# DDR4.net
KiCad netlist of a schematic drawn in Altium Designer
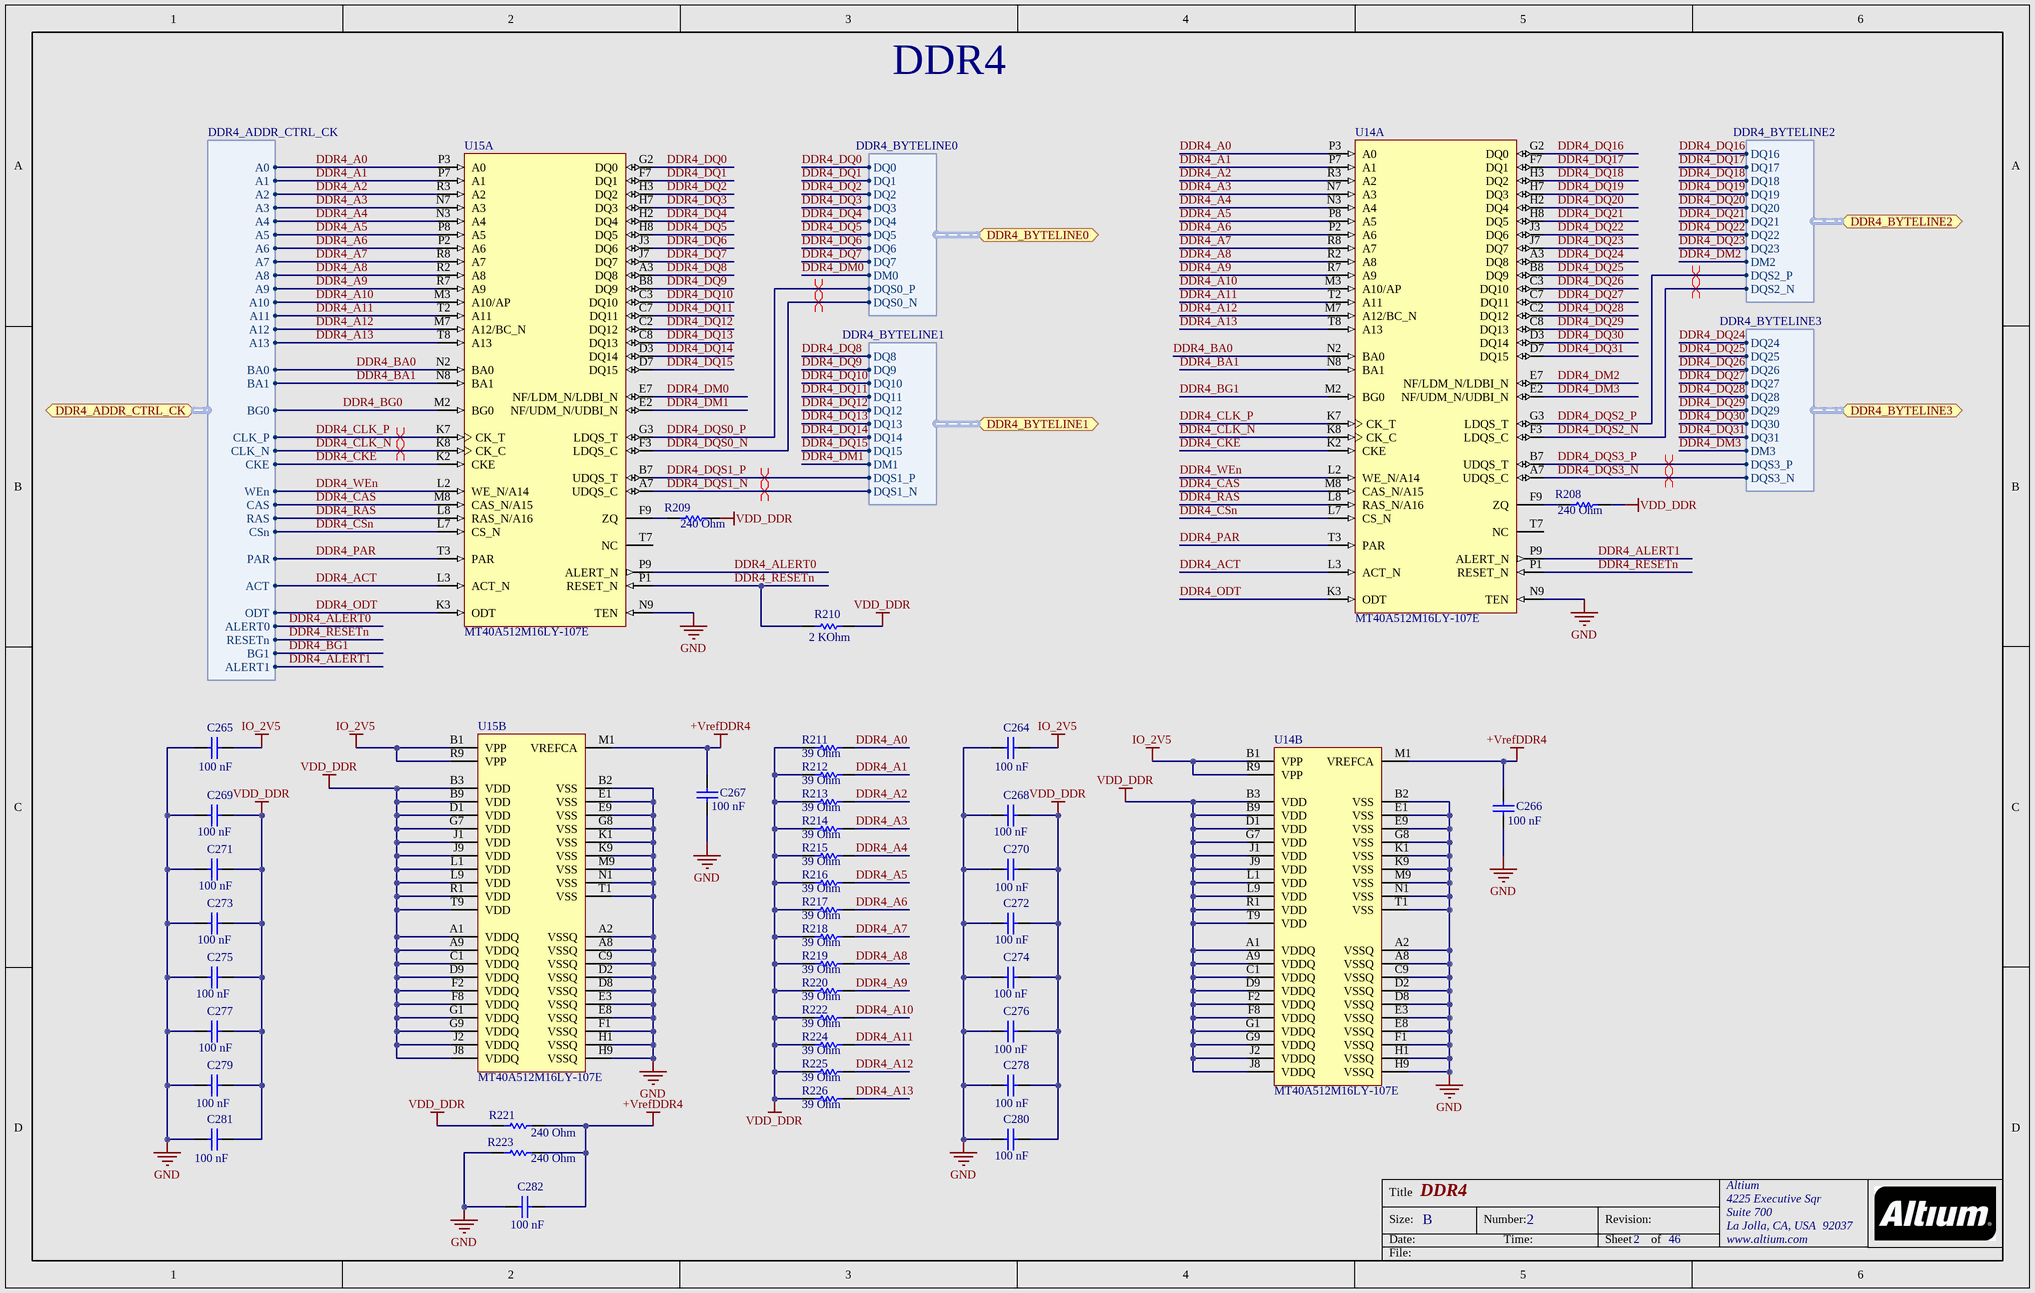
[diagram p0: DDR4.SchDoc]

(export (version "E")
  (design (tool "Eeschema 10.0.6"))
  (components
    (comp (ref "C264")
      (value "GRM033R60J104KE19D")
      (footprint "CAPC0603X33X15LL03T05")
      (description "Chip Capacitor, 100 nF, +/- 10%, 6.3 V, -55 to 85 degC, 0201 (0603 Metric), RoHS, Tape and Reel")
      (fields
        (field (name "TOLERANCE") "10%")
        (field (name "CAPACITANCE") "100 nF")
        (field (name "MANUFACTURER") "Basic Passives")
      )
      (libsource (lib "Altium Content Vault") (part "CAP-NP-2"))
    )
    (comp (ref "C265")
      (value "GRM033R60J104KE19D")
      (footprint "CAPC0603X33X15LL03T05")
      (description "Chip Capacitor, 100 nF, +/- 10%, 6.3 V, -55 to 85 degC, 0201 (0603 Metric), RoHS, Tape and Reel")
      (fields
        (field (name "TOLERANCE") "10%")
        (field (name "CAPACITANCE") "100 nF")
        (field (name "MANUFACTURER") "Basic Passives")
      )
      (libsource (lib "Altium Content Vault") (part "CAP-NP-2"))
    )
    (comp (ref "C266")
      (value "GRM033R60J104KE19D")
      (footprint "CAPC0603X33X15LL03T05")
      (description "Chip Capacitor, 100 nF, +/- 10%, 6.3 V, -55 to 85 degC, 0201 (0603 Metric), RoHS, Tape and Reel")
      (fields
        (field (name "TOLERANCE") "10%")
        (field (name "CAPACITANCE") "100 nF")
        (field (name "MANUFACTURER") "Basic Passives")
      )
      (libsource (lib "Altium Content Vault") (part "CAP-NP-2"))
    )
    (comp (ref "C267")
      (value "GRM033R60J104KE19D")
      (footprint "CAPC0603X33X15LL03T05")
      (description "Chip Capacitor, 100 nF, +/- 10%, 6.3 V, -55 to 85 degC, 0201 (0603 Metric), RoHS, Tape and Reel")
      (fields
        (field (name "TOLERANCE") "10%")
        (field (name "CAPACITANCE") "100 nF")
        (field (name "MANUFACTURER") "Basic Passives")
      )
      (libsource (lib "Altium Content Vault") (part "CAP-NP-2"))
    )
    (comp (ref "C268")
      (value "GRM033R60J104KE19D")
      (footprint "CAPC0603X33X15LL03T05")
      (description "Chip Capacitor, 100 nF, +/- 10%, 6.3 V, -55 to 85 degC, 0201 (0603 Metric), RoHS, Tape and Reel")
      (fields
        (field (name "TOLERANCE") "10%")
        (field (name "CAPACITANCE") "100 nF")
        (field (name "MANUFACTURER") "Basic Passives")
      )
      (libsource (lib "Altium Content Vault") (part "CAP-NP-2"))
    )
    (comp (ref "C269")
      (value "GRM033R60J104KE19D")
      (footprint "CAPC0603X33X15LL03T05")
      (description "Chip Capacitor, 100 nF, +/- 10%, 6.3 V, -55 to 85 degC, 0201 (0603 Metric), RoHS, Tape and Reel")
      (fields
        (field (name "TOLERANCE") "10%")
        (field (name "CAPACITANCE") "100 nF")
        (field (name "MANUFACTURER") "Basic Passives")
      )
      (libsource (lib "Altium Content Vault") (part "CAP-NP-2"))
    )
    (comp (ref "C270")
      (value "GRM033R60J104KE19D")
      (footprint "CAPC0603X33X15LL03T05")
      (description "Chip Capacitor, 100 nF, +/- 10%, 6.3 V, -55 to 85 degC, 0201 (0603 Metric), RoHS, Tape and Reel")
      (fields
        (field (name "TOLERANCE") "10%")
        (field (name "CAPACITANCE") "100 nF")
        (field (name "MANUFACTURER") "Basic Passives")
      )
      (libsource (lib "Altium Content Vault") (part "CAP-NP-2"))
    )
    (comp (ref "C271")
      (value "GRM033R60J104KE19D")
      (footprint "CAPC0603X33X15LL03T05")
      (description "Chip Capacitor, 100 nF, +/- 10%, 6.3 V, -55 to 85 degC, 0201 (0603 Metric), RoHS, Tape and Reel")
      (fields
        (field (name "TOLERANCE") "10%")
        (field (name "CAPACITANCE") "100 nF")
        (field (name "MANUFACTURER") "Basic Passives")
      )
      (libsource (lib "Altium Content Vault") (part "CAP-NP-2"))
    )
    (comp (ref "C272")
      (value "GRM033R60J104KE19D")
      (footprint "CAPC0603X33X15LL03T05")
      (description "Chip Capacitor, 100 nF, +/- 10%, 6.3 V, -55 to 85 degC, 0201 (0603 Metric), RoHS, Tape and Reel")
      (fields
        (field (name "TOLERANCE") "10%")
        (field (name "CAPACITANCE") "100 nF")
        (field (name "MANUFACTURER") "Basic Passives")
      )
      (libsource (lib "Altium Content Vault") (part "CAP-NP-2"))
    )
    (comp (ref "C273")
      (value "GRM033R60J104KE19D")
      (footprint "CAPC0603X33X15LL03T05")
      (description "Chip Capacitor, 100 nF, +/- 10%, 6.3 V, -55 to 85 degC, 0201 (0603 Metric), RoHS, Tape and Reel")
      (fields
        (field (name "TOLERANCE") "10%")
        (field (name "CAPACITANCE") "100 nF")
        (field (name "MANUFACTURER") "Basic Passives")
      )
      (libsource (lib "Altium Content Vault") (part "CAP-NP-2"))
    )
    (comp (ref "C274")
      (value "GRM033R60J104KE19D")
      (footprint "CAPC0603X33X15LL03T05")
      (description "Chip Capacitor, 100 nF, +/- 10%, 6.3 V, -55 to 85 degC, 0201 (0603 Metric), RoHS, Tape and Reel")
      (fields
        (field (name "TOLERANCE") "10%")
        (field (name "CAPACITANCE") "100 nF")
        (field (name "MANUFACTURER") "Basic Passives")
      )
      (libsource (lib "Altium Content Vault") (part "CAP-NP-2"))
    )
    (comp (ref "C275")
      (value "GRM033R60J104KE19D")
      (footprint "CAPC0603X33X15LL03T05")
      (description "Chip Capacitor, 100 nF, +/- 10%, 6.3 V, -55 to 85 degC, 0201 (0603 Metric), RoHS, Tape and Reel")
      (fields
        (field (name "TOLERANCE") "10%")
        (field (name "CAPACITANCE") "100 nF")
        (field (name "MANUFACTURER") "Basic Passives")
      )
      (libsource (lib "Altium Content Vault") (part "CAP-NP-2"))
    )
    (comp (ref "C276")
      (value "GRM033R60J104KE19D")
      (footprint "CAPC0603X33X15LL03T05")
      (description "Chip Capacitor, 100 nF, +/- 10%, 6.3 V, -55 to 85 degC, 0201 (0603 Metric), RoHS, Tape and Reel")
      (fields
        (field (name "TOLERANCE") "10%")
        (field (name "CAPACITANCE") "100 nF")
        (field (name "MANUFACTURER") "Basic Passives")
      )
      (libsource (lib "Altium Content Vault") (part "CAP-NP-2"))
    )
    (comp (ref "C277")
      (value "GRM033R60J104KE19D")
      (footprint "CAPC0603X33X15LL03T05")
      (description "Chip Capacitor, 100 nF, +/- 10%, 6.3 V, -55 to 85 degC, 0201 (0603 Metric), RoHS, Tape and Reel")
      (fields
        (field (name "TOLERANCE") "10%")
        (field (name "CAPACITANCE") "100 nF")
        (field (name "MANUFACTURER") "Basic Passives")
      )
      (libsource (lib "Altium Content Vault") (part "CAP-NP-2"))
    )
    (comp (ref "C278")
      (value "GRM033R60J104KE19D")
      (footprint "CAPC0603X33X15LL03T05")
      (description "Chip Capacitor, 100 nF, +/- 10%, 6.3 V, -55 to 85 degC, 0201 (0603 Metric), RoHS, Tape and Reel")
      (fields
        (field (name "TOLERANCE") "10%")
        (field (name "CAPACITANCE") "100 nF")
        (field (name "MANUFACTURER") "Basic Passives")
      )
      (libsource (lib "Altium Content Vault") (part "CAP-NP-2"))
    )
    (comp (ref "C279")
      (value "GRM033R60J104KE19D")
      (footprint "CAPC0603X33X15LL03T05")
      (description "Chip Capacitor, 100 nF, +/- 10%, 6.3 V, -55 to 85 degC, 0201 (0603 Metric), RoHS, Tape and Reel")
      (fields
        (field (name "TOLERANCE") "10%")
        (field (name "CAPACITANCE") "100 nF")
        (field (name "MANUFACTURER") "Basic Passives")
      )
      (libsource (lib "Altium Content Vault") (part "CAP-NP-2"))
    )
    (comp (ref "C280")
      (value "GRM033R60J104KE19D")
      (footprint "CAPC0603X33X15LL03T05")
      (description "Chip Capacitor, 100 nF, +/- 10%, 6.3 V, -55 to 85 degC, 0201 (0603 Metric), RoHS, Tape and Reel")
      (fields
        (field (name "TOLERANCE") "10%")
        (field (name "CAPACITANCE") "100 nF")
        (field (name "MANUFACTURER") "Basic Passives")
      )
      (libsource (lib "Altium Content Vault") (part "CAP-NP-2"))
    )
    (comp (ref "C281")
      (value "GRM033R60J104KE19D")
      (footprint "CAPC0603X33X15LL03T05")
      (description "Chip Capacitor, 100 nF, +/- 10%, 6.3 V, -55 to 85 degC, 0201 (0603 Metric), RoHS, Tape and Reel")
      (fields
        (field (name "TOLERANCE") "10%")
        (field (name "CAPACITANCE") "100 nF")
        (field (name "MANUFACTURER") "Basic Passives")
      )
      (libsource (lib "Altium Content Vault") (part "CAP-NP-2"))
    )
    (comp (ref "C282")
      (value "GRM033R60J104KE19D")
      (footprint "CAPC0603X33X15LL03T05")
      (description "Chip Capacitor, 100 nF, +/- 10%, 6.3 V, -55 to 85 degC, 0201 (0603 Metric), RoHS, Tape and Reel")
      (fields
        (field (name "TOLERANCE") "10%")
        (field (name "CAPACITANCE") "100 nF")
        (field (name "MANUFACTURER") "Basic Passives")
      )
      (libsource (lib "Altium Content Vault") (part "CAP-NP-2"))
    )
    (comp (ref "R208")
      (value "ERJ-2RKF2400X")
      (footprint "RESC1005X40X25NL05T05")
      (description "Chip Resistor, 240 Ohm, +/- 1%, 100 mW, -55 to 155 degC, 0402 (1005 Metric), RoHS, Tape and Reel")
      (fields (field (name "TOLERANCE") "1%") (field (name "RESISTANCE") "240 Ohm"))
      (libsource (lib "Altium Content Vault") (part "RES-2"))
    )
    (comp (ref "R209")
      (value "ERJ-2RKF2400X")
      (footprint "RESC1005X40X25NL05T05")
      (description "Chip Resistor, 240 Ohm, +/- 1%, 100 mW, -55 to 155 degC, 0402 (1005 Metric), RoHS, Tape and Reel")
      (fields (field (name "TOLERANCE") "1%") (field (name "RESISTANCE") "240 Ohm"))
      (libsource (lib "Altium Content Vault") (part "RES-2"))
    )
    (comp (ref "R210")
      (value "ERJ-2RKF2001X")
      (footprint "RESC1005X40X25NL05T05")
      (description "Chip Resistor, 2 KOhm, +/- 1%, 100 mW, -55 to 155 degC, 0402 (1005 Metric), RoHS, Tape and Reel")
      (fields
        (field (name "TOLERANCE") "1%")
        (field (name "RESISTANCE") "2 KOhm")
        (field (name "MANUFACTURER") "Basic Passives")
      )
      (libsource (lib "Altium Content Vault") (part "RES-2"))
    )
    (comp (ref "R211")
      (value "RC0402JR-0739RL")
      (footprint "RESC1005X40X25NL5T10")
      (description "Chip Resistor, 39 Ohm, +/- 5%, 0.063 W, -55 to 155 degC, 0402 (1005 Metric), RoHS, Tape and Reel")
      (fields (field (name "TOLERANCE") "5%") (field (name "RESISTANCE") "39 Ohm"))
      (libsource (lib "Altium Content Vault") (part "CMP-2002-07994-2"))
    )
    (comp (ref "R212")
      (value "RC0402JR-0739RL")
      (footprint "RESC1005X40X25NL5T10")
      (description "Chip Resistor, 39 Ohm, +/- 5%, 0.063 W, -55 to 155 degC, 0402 (1005 Metric), RoHS, Tape and Reel")
      (fields (field (name "TOLERANCE") "5%") (field (name "RESISTANCE") "39 Ohm"))
      (libsource (lib "Altium Content Vault") (part "CMP-2002-07994-2"))
    )
    (comp (ref "R213")
      (value "RC0402JR-0739RL")
      (footprint "RESC1005X40X25NL5T10")
      (description "Chip Resistor, 39 Ohm, +/- 5%, 0.063 W, -55 to 155 degC, 0402 (1005 Metric), RoHS, Tape and Reel")
      (fields (field (name "TOLERANCE") "5%") (field (name "RESISTANCE") "39 Ohm"))
      (libsource (lib "Altium Content Vault") (part "CMP-2002-07994-2"))
    )
    (comp (ref "R214")
      (value "RC0402JR-0739RL")
      (footprint "RESC1005X40X25NL5T10")
      (description "Chip Resistor, 39 Ohm, +/- 5%, 0.063 W, -55 to 155 degC, 0402 (1005 Metric), RoHS, Tape and Reel")
      (fields (field (name "TOLERANCE") "5%") (field (name "RESISTANCE") "39 Ohm"))
      (libsource (lib "Altium Content Vault") (part "CMP-2002-07994-2"))
    )
    (comp (ref "R215")
      (value "RC0402JR-0739RL")
      (footprint "RESC1005X40X25NL5T10")
      (description "Chip Resistor, 39 Ohm, +/- 5%, 0.063 W, -55 to 155 degC, 0402 (1005 Metric), RoHS, Tape and Reel")
      (fields (field (name "TOLERANCE") "5%") (field (name "RESISTANCE") "39 Ohm"))
      (libsource (lib "Altium Content Vault") (part "CMP-2002-07994-2"))
    )
    (comp (ref "R216")
      (value "RC0402JR-0739RL")
      (footprint "RESC1005X40X25NL5T10")
      (description "Chip Resistor, 39 Ohm, +/- 5%, 0.063 W, -55 to 155 degC, 0402 (1005 Metric), RoHS, Tape and Reel")
      (fields (field (name "TOLERANCE") "5%") (field (name "RESISTANCE") "39 Ohm"))
      (libsource (lib "Altium Content Vault") (part "CMP-2002-07994-2"))
    )
    (comp (ref "R217")
      (value "RC0402JR-0739RL")
      (footprint "RESC1005X40X25NL5T10")
      (description "Chip Resistor, 39 Ohm, +/- 5%, 0.063 W, -55 to 155 degC, 0402 (1005 Metric), RoHS, Tape and Reel")
      (fields (field (name "TOLERANCE") "5%") (field (name "RESISTANCE") "39 Ohm"))
      (libsource (lib "Altium Content Vault") (part "CMP-2002-07994-2"))
    )
    (comp (ref "R218")
      (value "RC0402JR-0739RL")
      (footprint "RESC1005X40X25NL5T10")
      (description "Chip Resistor, 39 Ohm, +/- 5%, 0.063 W, -55 to 155 degC, 0402 (1005 Metric), RoHS, Tape and Reel")
      (fields (field (name "TOLERANCE") "5%") (field (name "RESISTANCE") "39 Ohm"))
      (libsource (lib "Altium Content Vault") (part "CMP-2002-07994-2"))
    )
    (comp (ref "R219")
      (value "RC0402JR-0739RL")
      (footprint "RESC1005X40X25NL5T10")
      (description "Chip Resistor, 39 Ohm, +/- 5%, 0.063 W, -55 to 155 degC, 0402 (1005 Metric), RoHS, Tape and Reel")
      (fields (field (name "TOLERANCE") "5%") (field (name "RESISTANCE") "39 Ohm"))
      (libsource (lib "Altium Content Vault") (part "CMP-2002-07994-2"))
    )
    (comp (ref "R220")
      (value "RC0402JR-0739RL")
      (footprint "RESC1005X40X25NL5T10")
      (description "Chip Resistor, 39 Ohm, +/- 5%, 0.063 W, -55 to 155 degC, 0402 (1005 Metric), RoHS, Tape and Reel")
      (fields (field (name "TOLERANCE") "5%") (field (name "RESISTANCE") "39 Ohm"))
      (libsource (lib "Altium Content Vault") (part "CMP-2002-07994-2"))
    )
    (comp (ref "R221")
      (value "ERJ-2RKF2400X")
      (footprint "RESC1005X40X25NL05T05")
      (description "Chip Resistor, 240 Ohm, +/- 1%, 100 mW, -55 to 155 degC, 0402 (1005 Metric), RoHS, Tape and Reel")
      (fields (field (name "TOLERANCE") "1%") (field (name "RESISTANCE") "240 Ohm"))
      (libsource (lib "Altium Content Vault") (part "RES-2"))
    )
    (comp (ref "R222")
      (value "RC0402JR-0739RL")
      (footprint "RESC1005X40X25NL5T10")
      (description "Chip Resistor, 39 Ohm, +/- 5%, 0.063 W, -55 to 155 degC, 0402 (1005 Metric), RoHS, Tape and Reel")
      (fields (field (name "TOLERANCE") "5%") (field (name "RESISTANCE") "39 Ohm"))
      (libsource (lib "Altium Content Vault") (part "CMP-2002-07994-2"))
    )
    (comp (ref "R223")
      (value "ERJ-2RKF2400X")
      (footprint "RESC1005X40X25NL05T05")
      (description "Chip Resistor, 240 Ohm, +/- 1%, 100 mW, -55 to 155 degC, 0402 (1005 Metric), RoHS, Tape and Reel")
      (fields (field (name "TOLERANCE") "1%") (field (name "RESISTANCE") "240 Ohm"))
      (libsource (lib "Altium Content Vault") (part "RES-2"))
    )
    (comp (ref "R224")
      (value "RC0402JR-0739RL")
      (footprint "RESC1005X40X25NL5T10")
      (description "Chip Resistor, 39 Ohm, +/- 5%, 0.063 W, -55 to 155 degC, 0402 (1005 Metric), RoHS, Tape and Reel")
      (fields (field (name "TOLERANCE") "5%") (field (name "RESISTANCE") "39 Ohm"))
      (libsource (lib "Altium Content Vault") (part "CMP-2002-07994-2"))
    )
    (comp (ref "R225")
      (value "RC0402JR-0739RL")
      (footprint "RESC1005X40X25NL5T10")
      (description "Chip Resistor, 39 Ohm, +/- 5%, 0.063 W, -55 to 155 degC, 0402 (1005 Metric), RoHS, Tape and Reel")
      (fields (field (name "TOLERANCE") "5%") (field (name "RESISTANCE") "39 Ohm"))
      (libsource (lib "Altium Content Vault") (part "CMP-2002-07994-2"))
    )
    (comp (ref "R226")
      (value "RC0402JR-0739RL")
      (footprint "RESC1005X40X25NL5T10")
      (description "Chip Resistor, 39 Ohm, +/- 5%, 0.063 W, -55 to 155 degC, 0402 (1005 Metric), RoHS, Tape and Reel")
      (fields (field (name "TOLERANCE") "5%") (field (name "RESISTANCE") "39 Ohm"))
      (libsource (lib "Altium Content Vault") (part "CMP-2002-07994-2"))
    )
    (comp (ref "U14")
      (value "MT40A512M16LY-107E")
      (footprint "MICT-LY-96_A")
      (description "8 Gb DDR4 SDRAM, 512 Meg x 16, 1.2 V, 0 to 95 degC, 96-Ball FBGA (LY), RoHS")
      (libsource (lib "Altium Content Vault") (part "CMP-1718-00002-1"))
    )
    (comp (ref "U15")
      (value "MT40A512M16LY-107E")
      (footprint "MICT-LY-96_A")
      (description "8 Gb DDR4 SDRAM, 512 Meg x 16, 1.2 V, 0 to 95 degC, 96-Ball FBGA (LY), RoHS")
      (libsource (lib "Altium Content Vault") (part "CMP-1718-00002-1"))
    )
  )
  (nets
    (net (code "6") (name "+VrefDDR4") (class "Default")
      (node (ref "C266") (pin "2") (pinfunction "2_2") (pintype "passive"))
      (node (ref "C267") (pin "2") (pinfunction "2_2") (pintype "passive"))
      (node (ref "C282") (pin "2") (pinfunction "2_2") (pintype "passive"))
      (node (ref "R221") (pin "2") (pinfunction "2_2") (pintype "passive"))
      (node (ref "R223") (pin "2") (pinfunction "2_2") (pintype "passive"))
      (node (ref "U14") (pin "M1") (pinfunction "VREFCA_M1") (pintype "passive"))
      (node (ref "U15") (pin "M1") (pinfunction "VREFCA_M1") (pintype "passive"))
    )
    (net (code "7") (name "/DDR4_A0") (class "Default")
      (node (ref "R211") (pin "2") (pinfunction "2_2") (pintype "passive"))
      (node (ref "U14") (pin "P3") (pinfunction "A0_P3") (pintype "input"))
      (node (ref "U15") (pin "P3") (pinfunction "A0_P3") (pintype "input"))
    )
    (net (code "8") (name "/DDR4_A1") (class "Default")
      (node (ref "R212") (pin "2") (pinfunction "2_2") (pintype "passive"))
      (node (ref "U14") (pin "P7") (pinfunction "A1_P7") (pintype "input"))
      (node (ref "U15") (pin "P7") (pinfunction "A1_P7") (pintype "input"))
    )
    (net (code "9") (name "/DDR4_A2") (class "Default")
      (node (ref "R213") (pin "2") (pinfunction "2_2") (pintype "passive"))
      (node (ref "U14") (pin "R3") (pinfunction "A2_R3") (pintype "input"))
      (node (ref "U15") (pin "R3") (pinfunction "A2_R3") (pintype "input"))
    )
    (net (code "10") (name "/DDR4_A3") (class "Default")
      (node (ref "R214") (pin "2") (pinfunction "2_2") (pintype "passive"))
      (node (ref "U14") (pin "N7") (pinfunction "A3_N7") (pintype "input"))
      (node (ref "U15") (pin "N7") (pinfunction "A3_N7") (pintype "input"))
    )
    (net (code "11") (name "/DDR4_A4") (class "Default")
      (node (ref "R215") (pin "2") (pinfunction "2_2") (pintype "passive"))
      (node (ref "U14") (pin "N3") (pinfunction "A4_N3") (pintype "input"))
      (node (ref "U15") (pin "N3") (pinfunction "A4_N3") (pintype "input"))
    )
    (net (code "12") (name "/DDR4_A5") (class "Default")
      (node (ref "R216") (pin "2") (pinfunction "2_2") (pintype "passive"))
      (node (ref "U14") (pin "P8") (pinfunction "A5_P8") (pintype "input"))
      (node (ref "U15") (pin "P8") (pinfunction "A5_P8") (pintype "input"))
    )
    (net (code "13") (name "/DDR4_A6") (class "Default")
      (node (ref "R217") (pin "2") (pinfunction "2_2") (pintype "passive"))
      (node (ref "U14") (pin "P2") (pinfunction "A6_P2") (pintype "input"))
      (node (ref "U15") (pin "P2") (pinfunction "A6_P2") (pintype "input"))
    )
    (net (code "14") (name "/DDR4_A7") (class "Default")
      (node (ref "R218") (pin "2") (pinfunction "2_2") (pintype "passive"))
      (node (ref "U14") (pin "R8") (pinfunction "A7_R8") (pintype "input"))
      (node (ref "U15") (pin "R8") (pinfunction "A7_R8") (pintype "input"))
    )
    (net (code "15") (name "/DDR4_A8") (class "Default")
      (node (ref "R219") (pin "2") (pinfunction "2_2") (pintype "passive"))
      (node (ref "U14") (pin "R2") (pinfunction "A8_R2") (pintype "input"))
      (node (ref "U15") (pin "R2") (pinfunction "A8_R2") (pintype "input"))
    )
    (net (code "16") (name "/DDR4_A9") (class "Default")
      (node (ref "R220") (pin "2") (pinfunction "2_2") (pintype "passive"))
      (node (ref "U14") (pin "R7") (pinfunction "A9_R7") (pintype "input"))
      (node (ref "U15") (pin "R7") (pinfunction "A9_R7") (pintype "input"))
    )
    (net (code "17") (name "/DDR4_A10") (class "Default")
      (node (ref "R222") (pin "2") (pinfunction "2_2") (pintype "passive"))
      (node (ref "U14") (pin "M3") (pinfunction "A10/AP_M3") (pintype "input"))
      (node (ref "U15") (pin "M3") (pinfunction "A10/AP_M3") (pintype "input"))
    )
    (net (code "18") (name "/DDR4_A11") (class "Default")
      (node (ref "R224") (pin "2") (pinfunction "2_2") (pintype "passive"))
      (node (ref "U14") (pin "T2") (pinfunction "A11_T2") (pintype "input"))
      (node (ref "U15") (pin "T2") (pinfunction "A11_T2") (pintype "input"))
    )
    (net (code "19") (name "/DDR4_A12") (class "Default")
      (node (ref "R225") (pin "2") (pinfunction "2_2") (pintype "passive"))
      (node (ref "U14") (pin "M7") (pinfunction "A12/BC_N_M7") (pintype "input"))
      (node (ref "U15") (pin "M7") (pinfunction "A12/BC_N_M7") (pintype "input"))
    )
    (net (code "20") (name "/DDR4_A13") (class "Default")
      (node (ref "R226") (pin "2") (pinfunction "2_2") (pintype "passive"))
      (node (ref "U14") (pin "T8") (pinfunction "A13_T8") (pintype "input"))
      (node (ref "U15") (pin "T8") (pinfunction "A13_T8") (pintype "input"))
    )
    (net (code "21") (name "/DDR4_ACT") (class "Default")
      (node (ref "U14") (pin "L3") (pinfunction "ACT_N_L3") (pintype "input"))
      (node (ref "U15") (pin "L3") (pinfunction "ACT_N_L3") (pintype "input"))
    )
    (net (code "22") (name "/DDR4_ALERT0") (class "Default")
      (node (ref "U15") (pin "P9") (pinfunction "ALERT_N_P9") (pintype "output"))
    )
    (net (code "23") (name "/DDR4_ALERT1") (class "Default")
      (node (ref "U14") (pin "P9") (pinfunction "ALERT_N_P9") (pintype "output"))
    )
    (net (code "24") (name "/DDR4_BA0") (class "Default")
      (node (ref "U14") (pin "N2") (pinfunction "BA0_N2") (pintype "input"))
      (node (ref "U15") (pin "N2") (pinfunction "BA0_N2") (pintype "input"))
    )
    (net (code "25") (name "/DDR4_BA1") (class "Default")
      (node (ref "U14") (pin "N8") (pinfunction "BA1_N8") (pintype "input"))
      (node (ref "U15") (pin "N8") (pinfunction "BA1_N8") (pintype "input"))
    )
    (net (code "26") (name "/DDR4_BG0") (class "Default")
      (node (ref "U15") (pin "M2") (pinfunction "BG0_M2") (pintype "input"))
    )
    (net (code "27") (name "/DDR4_BG1") (class "Default")
      (node (ref "U14") (pin "M2") (pinfunction "BG0_M2") (pintype "input"))
    )
    (net (code "28") (name "/DDR4_CAS") (class "Default")
      (node (ref "U14") (pin "M8") (pinfunction "CAS_N/A15_M8") (pintype "input"))
      (node (ref "U15") (pin "M8") (pinfunction "CAS_N/A15_M8") (pintype "input"))
    )
    (net (code "29") (name "/DDR4_CKE") (class "Default")
      (node (ref "U14") (pin "K2") (pinfunction "CKE_K2") (pintype "input"))
      (node (ref "U15") (pin "K2") (pinfunction "CKE_K2") (pintype "input"))
    )
    (net (code "30") (name "/DDR4_CLK_N") (class "Default")
      (node (ref "U14") (pin "K8") (pinfunction "CK_C_K8") (pintype "input"))
      (node (ref "U15") (pin "K8") (pinfunction "CK_C_K8") (pintype "input"))
    )
    (net (code "31") (name "/DDR4_CLK_P") (class "Default")
      (node (ref "U14") (pin "K7") (pinfunction "CK_T_K7") (pintype "input"))
      (node (ref "U15") (pin "K7") (pinfunction "CK_T_K7") (pintype "input"))
    )
    (net (code "32") (name "/DDR4_CSn") (class "Default")
      (node (ref "U14") (pin "L7") (pinfunction "CS_N_L7") (pintype "input"))
      (node (ref "U15") (pin "L7") (pinfunction "CS_N_L7") (pintype "input"))
    )
    (net (code "33") (name "/DDR4_DM0") (class "Default")
      (node (ref "U15") (pin "E7") (pinfunction "NF/LDM_N/LDBI_N_E7") (pintype "bidirectional"))
    )
    (net (code "34") (name "/DDR4_DM1") (class "Default")
      (node (ref "U15") (pin "E2") (pinfunction "NF/UDM_N/UDBI_N_E2") (pintype "bidirectional"))
    )
    (net (code "35") (name "/DDR4_DM2") (class "Default")
      (node (ref "U14") (pin "E7") (pinfunction "NF/LDM_N/LDBI_N_E7") (pintype "bidirectional"))
    )
    (net (code "36") (name "/DDR4_DM3") (class "Default")
      (node (ref "U14") (pin "E2") (pinfunction "NF/UDM_N/UDBI_N_E2") (pintype "bidirectional"))
    )
    (net (code "37") (name "/DDR4_DQ0") (class "Default")
      (node (ref "U15") (pin "G2") (pinfunction "DQ0_G2") (pintype "bidirectional"))
    )
    (net (code "38") (name "/DDR4_DQ1") (class "Default")
      (node (ref "U15") (pin "F7") (pinfunction "DQ1_F7") (pintype "bidirectional"))
    )
    (net (code "39") (name "/DDR4_DQ2") (class "Default")
      (node (ref "U15") (pin "H3") (pinfunction "DQ2_H3") (pintype "bidirectional"))
    )
    (net (code "40") (name "/DDR4_DQ3") (class "Default")
      (node (ref "U15") (pin "H7") (pinfunction "DQ3_H7") (pintype "bidirectional"))
    )
    (net (code "41") (name "/DDR4_DQ4") (class "Default")
      (node (ref "U15") (pin "H2") (pinfunction "DQ4_H2") (pintype "bidirectional"))
    )
    (net (code "42") (name "/DDR4_DQ5") (class "Default")
      (node (ref "U15") (pin "H8") (pinfunction "DQ5_H8") (pintype "bidirectional"))
    )
    (net (code "43") (name "/DDR4_DQ6") (class "Default")
      (node (ref "U15") (pin "J3") (pinfunction "DQ6_J3") (pintype "bidirectional"))
    )
    (net (code "44") (name "/DDR4_DQ7") (class "Default")
      (node (ref "U15") (pin "J7") (pinfunction "DQ7_J7") (pintype "bidirectional"))
    )
    (net (code "45") (name "/DDR4_DQ8") (class "Default")
      (node (ref "U15") (pin "A3") (pinfunction "DQ8_A3") (pintype "bidirectional"))
    )
    (net (code "46") (name "/DDR4_DQ9") (class "Default")
      (node (ref "U15") (pin "B8") (pinfunction "DQ9_B8") (pintype "bidirectional"))
    )
    (net (code "47") (name "/DDR4_DQ10") (class "Default")
      (node (ref "U15") (pin "C3") (pinfunction "DQ10_C3") (pintype "bidirectional"))
    )
    (net (code "48") (name "/DDR4_DQ11") (class "Default")
      (node (ref "U15") (pin "C7") (pinfunction "DQ11_C7") (pintype "bidirectional"))
    )
    (net (code "49") (name "/DDR4_DQ12") (class "Default")
      (node (ref "U15") (pin "C2") (pinfunction "DQ12_C2") (pintype "bidirectional"))
    )
    (net (code "50") (name "/DDR4_DQ13") (class "Default")
      (node (ref "U15") (pin "C8") (pinfunction "DQ13_C8") (pintype "bidirectional"))
    )
    (net (code "51") (name "/DDR4_DQ14") (class "Default")
      (node (ref "U15") (pin "D3") (pinfunction "DQ14_D3") (pintype "bidirectional"))
    )
    (net (code "52") (name "/DDR4_DQ15") (class "Default")
      (node (ref "U15") (pin "D7") (pinfunction "DQ15_D7") (pintype "bidirectional"))
    )
    (net (code "53") (name "/DDR4_DQ16") (class "Default")
      (node (ref "U14") (pin "G2") (pinfunction "DQ0_G2") (pintype "bidirectional"))
    )
    (net (code "54") (name "/DDR4_DQ17") (class "Default")
      (node (ref "U14") (pin "F7") (pinfunction "DQ1_F7") (pintype "bidirectional"))
    )
    (net (code "55") (name "/DDR4_DQ18") (class "Default")
      (node (ref "U14") (pin "H3") (pinfunction "DQ2_H3") (pintype "bidirectional"))
    )
    (net (code "56") (name "/DDR4_DQ19") (class "Default")
      (node (ref "U14") (pin "H7") (pinfunction "DQ3_H7") (pintype "bidirectional"))
    )
    (net (code "57") (name "/DDR4_DQ20") (class "Default")
      (node (ref "U14") (pin "H2") (pinfunction "DQ4_H2") (pintype "bidirectional"))
    )
    (net (code "58") (name "/DDR4_DQ21") (class "Default")
      (node (ref "U14") (pin "H8") (pinfunction "DQ5_H8") (pintype "bidirectional"))
    )
    (net (code "59") (name "/DDR4_DQ22") (class "Default")
      (node (ref "U14") (pin "J3") (pinfunction "DQ6_J3") (pintype "bidirectional"))
    )
    (net (code "60") (name "/DDR4_DQ23") (class "Default")
      (node (ref "U14") (pin "J7") (pinfunction "DQ7_J7") (pintype "bidirectional"))
    )
    (net (code "61") (name "/DDR4_DQ24") (class "Default")
      (node (ref "U14") (pin "A3") (pinfunction "DQ8_A3") (pintype "bidirectional"))
    )
    (net (code "62") (name "/DDR4_DQ25") (class "Default")
      (node (ref "U14") (pin "B8") (pinfunction "DQ9_B8") (pintype "bidirectional"))
    )
    (net (code "63") (name "/DDR4_DQ26") (class "Default")
      (node (ref "U14") (pin "C3") (pinfunction "DQ10_C3") (pintype "bidirectional"))
    )
    (net (code "64") (name "/DDR4_DQ27") (class "Default")
      (node (ref "U14") (pin "C7") (pinfunction "DQ11_C7") (pintype "bidirectional"))
    )
    (net (code "65") (name "/DDR4_DQ28") (class "Default")
      (node (ref "U14") (pin "C2") (pinfunction "DQ12_C2") (pintype "bidirectional"))
    )
    (net (code "66") (name "/DDR4_DQ29") (class "Default")
      (node (ref "U14") (pin "C8") (pinfunction "DQ13_C8") (pintype "bidirectional"))
    )
    (net (code "67") (name "/DDR4_DQ30") (class "Default")
      (node (ref "U14") (pin "D3") (pinfunction "DQ14_D3") (pintype "bidirectional"))
    )
    (net (code "68") (name "/DDR4_DQ31") (class "Default")
      (node (ref "U14") (pin "D7") (pinfunction "DQ15_D7") (pintype "bidirectional"))
    )
    (net (code "69") (name "/DDR4_DQS0_N") (class "Default")
      (node (ref "U15") (pin "F3") (pinfunction "LDQS_C_F3") (pintype "bidirectional"))
    )
    (net (code "70") (name "/DDR4_DQS0_P") (class "Default")
      (node (ref "U15") (pin "G3") (pinfunction "LDQS_T_G3") (pintype "bidirectional"))
    )
    (net (code "71") (name "/DDR4_DQS1_N") (class "Default")
      (node (ref "U15") (pin "A7") (pinfunction "UDQS_C_A7") (pintype "bidirectional"))
    )
    (net (code "72") (name "/DDR4_DQS1_P") (class "Default")
      (node (ref "U15") (pin "B7") (pinfunction "UDQS_T_B7") (pintype "bidirectional"))
    )
    (net (code "73") (name "/DDR4_DQS2_N") (class "Default")
      (node (ref "U14") (pin "F3") (pinfunction "LDQS_C_F3") (pintype "bidirectional"))
    )
    (net (code "74") (name "/DDR4_DQS2_P") (class "Default")
      (node (ref "U14") (pin "G3") (pinfunction "LDQS_T_G3") (pintype "bidirectional"))
    )
    (net (code "75") (name "/DDR4_DQS3_N") (class "Default")
      (node (ref "U14") (pin "A7") (pinfunction "UDQS_C_A7") (pintype "bidirectional"))
    )
    (net (code "76") (name "/DDR4_DQS3_P") (class "Default")
      (node (ref "U14") (pin "B7") (pinfunction "UDQS_T_B7") (pintype "bidirectional"))
    )
    (net (code "77") (name "/DDR4_ODT") (class "Default")
      (node (ref "U14") (pin "K3") (pinfunction "ODT_K3") (pintype "input"))
      (node (ref "U15") (pin "K3") (pinfunction "ODT_K3") (pintype "input"))
    )
    (net (code "78") (name "/DDR4_PAR") (class "Default")
      (node (ref "U14") (pin "T3") (pinfunction "PAR_T3") (pintype "input"))
      (node (ref "U15") (pin "T3") (pinfunction "PAR_T3") (pintype "input"))
    )
    (net (code "79") (name "/DDR4_RAS") (class "Default")
      (node (ref "U14") (pin "L8") (pinfunction "RAS_N/A16_L8") (pintype "input"))
      (node (ref "U15") (pin "L8") (pinfunction "RAS_N/A16_L8") (pintype "input"))
    )
    (net (code "80") (name "/DDR4_RESETn") (class "Default")
      (node (ref "R210") (pin "1") (pinfunction "1_1") (pintype "passive"))
      (node (ref "U14") (pin "P1") (pinfunction "RESET_N_P1") (pintype "input"))
      (node (ref "U15") (pin "P1") (pinfunction "RESET_N_P1") (pintype "input"))
    )
    (net (code "81") (name "/DDR4_WEn") (class "Default")
      (node (ref "U14") (pin "L2") (pinfunction "WE_N/A14_L2") (pintype "input"))
      (node (ref "U15") (pin "L2") (pinfunction "WE_N/A14_L2") (pintype "input"))
    )
    (net (code "87") (name "GND") (class "Default")
      (node (ref "C264") (pin "1") (pinfunction "1_1") (pintype "passive"))
      (node (ref "C265") (pin "1") (pinfunction "1_1") (pintype "passive"))
      (node (ref "C266") (pin "1") (pinfunction "1_1") (pintype "passive"))
      (node (ref "C267") (pin "1") (pinfunction "1_1") (pintype "passive"))
      (node (ref "C268") (pin "1") (pinfunction "1_1") (pintype "passive"))
      (node (ref "C269") (pin "1") (pinfunction "1_1") (pintype "passive"))
      (node (ref "C270") (pin "1") (pinfunction "1_1") (pintype "passive"))
      (node (ref "C271") (pin "1") (pinfunction "1_1") (pintype "passive"))
      (node (ref "C272") (pin "1") (pinfunction "1_1") (pintype "passive"))
      (node (ref "C273") (pin "1") (pinfunction "1_1") (pintype "passive"))
      (node (ref "C274") (pin "1") (pinfunction "1_1") (pintype "passive"))
      (node (ref "C275") (pin "1") (pinfunction "1_1") (pintype "passive"))
      (node (ref "C276") (pin "1") (pinfunction "1_1") (pintype "passive"))
      (node (ref "C277") (pin "1") (pinfunction "1_1") (pintype "passive"))
      (node (ref "C278") (pin "1") (pinfunction "1_1") (pintype "passive"))
      (node (ref "C279") (pin "1") (pinfunction "1_1") (pintype "passive"))
      (node (ref "C280") (pin "1") (pinfunction "1_1") (pintype "passive"))
      (node (ref "C281") (pin "1") (pinfunction "1_1") (pintype "passive"))
      (node (ref "C282") (pin "1") (pinfunction "1_1") (pintype "passive"))
      (node (ref "R223") (pin "1") (pinfunction "1_1") (pintype "passive"))
      (node (ref "U14") (pin "A2") (pinfunction "VSSQ_A2") (pintype "power_in"))
      (node (ref "U14") (pin "A8") (pinfunction "VSSQ_A8") (pintype "power_in"))
      (node (ref "U14") (pin "B2") (pinfunction "VSS_B2") (pintype "power_in"))
      (node (ref "U14") (pin "C9") (pinfunction "VSSQ_C9") (pintype "power_in"))
      (node (ref "U14") (pin "D2") (pinfunction "VSSQ_D2") (pintype "power_in"))
      (node (ref "U14") (pin "D8") (pinfunction "VSSQ_D8") (pintype "power_in"))
      (node (ref "U14") (pin "E1") (pinfunction "VSS_E1") (pintype "power_in"))
      (node (ref "U14") (pin "E3") (pinfunction "VSSQ_E3") (pintype "power_in"))
      (node (ref "U14") (pin "E8") (pinfunction "VSSQ_E8") (pintype "power_in"))
      (node (ref "U14") (pin "E9") (pinfunction "VSS_E9") (pintype "power_in"))
      (node (ref "U14") (pin "F1") (pinfunction "VSSQ_F1") (pintype "power_in"))
      (node (ref "U14") (pin "G8") (pinfunction "VSS_G8") (pintype "power_in"))
      (node (ref "U14") (pin "H1") (pinfunction "VSSQ_H1") (pintype "power_in"))
      (node (ref "U14") (pin "H9") (pinfunction "VSSQ_H9") (pintype "power_in"))
      (node (ref "U14") (pin "K1") (pinfunction "VSS_K1") (pintype "power_in"))
      (node (ref "U14") (pin "K9") (pinfunction "VSS_K9") (pintype "power_in"))
      (node (ref "U14") (pin "M9") (pinfunction "VSS_M9") (pintype "power_in"))
      (node (ref "U14") (pin "N1") (pinfunction "VSS_N1") (pintype "power_in"))
      (node (ref "U14") (pin "N9") (pinfunction "TEN_N9") (pintype "input"))
      (node (ref "U14") (pin "T1") (pinfunction "VSS_T1") (pintype "power_in"))
      (node (ref "U15") (pin "A2") (pinfunction "VSSQ_A2") (pintype "power_in"))
      (node (ref "U15") (pin "A8") (pinfunction "VSSQ_A8") (pintype "power_in"))
      (node (ref "U15") (pin "B2") (pinfunction "VSS_B2") (pintype "power_in"))
      (node (ref "U15") (pin "C9") (pinfunction "VSSQ_C9") (pintype "power_in"))
      (node (ref "U15") (pin "D2") (pinfunction "VSSQ_D2") (pintype "power_in"))
      (node (ref "U15") (pin "D8") (pinfunction "VSSQ_D8") (pintype "power_in"))
      (node (ref "U15") (pin "E1") (pinfunction "VSS_E1") (pintype "power_in"))
      (node (ref "U15") (pin "E3") (pinfunction "VSSQ_E3") (pintype "power_in"))
      (node (ref "U15") (pin "E8") (pinfunction "VSSQ_E8") (pintype "power_in"))
      (node (ref "U15") (pin "E9") (pinfunction "VSS_E9") (pintype "power_in"))
      (node (ref "U15") (pin "F1") (pinfunction "VSSQ_F1") (pintype "power_in"))
      (node (ref "U15") (pin "G8") (pinfunction "VSS_G8") (pintype "power_in"))
      (node (ref "U15") (pin "H1") (pinfunction "VSSQ_H1") (pintype "power_in"))
      (node (ref "U15") (pin "H9") (pinfunction "VSSQ_H9") (pintype "power_in"))
      (node (ref "U15") (pin "K1") (pinfunction "VSS_K1") (pintype "power_in"))
      (node (ref "U15") (pin "K9") (pinfunction "VSS_K9") (pintype "power_in"))
      (node (ref "U15") (pin "M9") (pinfunction "VSS_M9") (pintype "power_in"))
      (node (ref "U15") (pin "N1") (pinfunction "VSS_N1") (pintype "power_in"))
      (node (ref "U15") (pin "N9") (pinfunction "TEN_N9") (pintype "input"))
      (node (ref "U15") (pin "T1") (pinfunction "VSS_T1") (pintype "power_in"))
    )
    (net (code "88") (name "IO_2V5") (class "Default")
      (node (ref "C264") (pin "2") (pinfunction "2_2") (pintype "passive"))
      (node (ref "C265") (pin "2") (pinfunction "2_2") (pintype "passive"))
      (node (ref "U14") (pin "B1") (pinfunction "VPP_B1") (pintype "power_in"))
      (node (ref "U14") (pin "R9") (pinfunction "VPP_R9") (pintype "power_in"))
      (node (ref "U15") (pin "B1") (pinfunction "VPP_B1") (pintype "power_in"))
      (node (ref "U15") (pin "R9") (pinfunction "VPP_R9") (pintype "power_in"))
    )
    (net (code "89") (name "Net-(U14A-ZQ)") (class "Default")
      (node (ref "R208") (pin "1") (pinfunction "1_1") (pintype "passive"))
      (node (ref "U14") (pin "F9") (pinfunction "ZQ_F9") (pintype "passive"))
    )
    (net (code "90") (name "Net-(U15A-ZQ)") (class "Default")
      (node (ref "R209") (pin "1") (pinfunction "1_1") (pintype "passive"))
      (node (ref "U15") (pin "F9") (pinfunction "ZQ_F9") (pintype "passive"))
    )
    (net (code "91") (name "VDD_DDR") (class "Default")
      (node (ref "C268") (pin "2") (pinfunction "2_2") (pintype "passive"))
      (node (ref "C269") (pin "2") (pinfunction "2_2") (pintype "passive"))
      (node (ref "C270") (pin "2") (pinfunction "2_2") (pintype "passive"))
      (node (ref "C271") (pin "2") (pinfunction "2_2") (pintype "passive"))
      (node (ref "C272") (pin "2") (pinfunction "2_2") (pintype "passive"))
      (node (ref "C273") (pin "2") (pinfunction "2_2") (pintype "passive"))
      (node (ref "C274") (pin "2") (pinfunction "2_2") (pintype "passive"))
      (node (ref "C275") (pin "2") (pinfunction "2_2") (pintype "passive"))
      (node (ref "C276") (pin "2") (pinfunction "2_2") (pintype "passive"))
      (node (ref "C277") (pin "2") (pinfunction "2_2") (pintype "passive"))
      (node (ref "C278") (pin "2") (pinfunction "2_2") (pintype "passive"))
      (node (ref "C279") (pin "2") (pinfunction "2_2") (pintype "passive"))
      (node (ref "C280") (pin "2") (pinfunction "2_2") (pintype "passive"))
      (node (ref "C281") (pin "2") (pinfunction "2_2") (pintype "passive"))
      (node (ref "R208") (pin "2") (pinfunction "2_2") (pintype "passive"))
      (node (ref "R209") (pin "2") (pinfunction "2_2") (pintype "passive"))
      (node (ref "R210") (pin "2") (pinfunction "2_2") (pintype "passive"))
      (node (ref "R211") (pin "1") (pinfunction "1_1") (pintype "passive"))
      (node (ref "R212") (pin "1") (pinfunction "1_1") (pintype "passive"))
      (node (ref "R213") (pin "1") (pinfunction "1_1") (pintype "passive"))
      (node (ref "R214") (pin "1") (pinfunction "1_1") (pintype "passive"))
      (node (ref "R215") (pin "1") (pinfunction "1_1") (pintype "passive"))
      (node (ref "R216") (pin "1") (pinfunction "1_1") (pintype "passive"))
      (node (ref "R217") (pin "1") (pinfunction "1_1") (pintype "passive"))
      (node (ref "R218") (pin "1") (pinfunction "1_1") (pintype "passive"))
      (node (ref "R219") (pin "1") (pinfunction "1_1") (pintype "passive"))
      (node (ref "R220") (pin "1") (pinfunction "1_1") (pintype "passive"))
      (node (ref "R221") (pin "1") (pinfunction "1_1") (pintype "passive"))
      (node (ref "R222") (pin "1") (pinfunction "1_1") (pintype "passive"))
      (node (ref "R224") (pin "1") (pinfunction "1_1") (pintype "passive"))
      (node (ref "R225") (pin "1") (pinfunction "1_1") (pintype "passive"))
      (node (ref "R226") (pin "1") (pinfunction "1_1") (pintype "passive"))
      (node (ref "U14") (pin "A1") (pinfunction "VDDQ_A1") (pintype "power_in"))
      (node (ref "U14") (pin "A9") (pinfunction "VDDQ_A9") (pintype "power_in"))
      (node (ref "U14") (pin "B3") (pinfunction "VDD_B3") (pintype "power_in"))
      (node (ref "U14") (pin "B9") (pinfunction "VDD_B9") (pintype "power_in"))
      (node (ref "U14") (pin "C1") (pinfunction "VDDQ_C1") (pintype "power_in"))
      (node (ref "U14") (pin "D1") (pinfunction "VDD_D1") (pintype "power_in"))
      (node (ref "U14") (pin "D9") (pinfunction "VDDQ_D9") (pintype "power_in"))
      (node (ref "U14") (pin "F2") (pinfunction "VDDQ_F2") (pintype "power_in"))
      (node (ref "U14") (pin "F8") (pinfunction "VDDQ_F8") (pintype "power_in"))
      (node (ref "U14") (pin "G1") (pinfunction "VDDQ_G1") (pintype "power_in"))
      (node (ref "U14") (pin "G7") (pinfunction "VDD_G7") (pintype "power_in"))
      (node (ref "U14") (pin "G9") (pinfunction "VDDQ_G9") (pintype "power_in"))
      (node (ref "U14") (pin "J1") (pinfunction "VDD_J1") (pintype "power_in"))
      (node (ref "U14") (pin "J2") (pinfunction "VDDQ_J2") (pintype "power_in"))
      (node (ref "U14") (pin "J8") (pinfunction "VDDQ_J8") (pintype "power_in"))
      (node (ref "U14") (pin "J9") (pinfunction "VDD_J9") (pintype "power_in"))
      (node (ref "U14") (pin "L1") (pinfunction "VDD_L1") (pintype "power_in"))
      (node (ref "U14") (pin "L9") (pinfunction "VDD_L9") (pintype "power_in"))
      (node (ref "U14") (pin "R1") (pinfunction "VDD_R1") (pintype "power_in"))
      (node (ref "U14") (pin "T9") (pinfunction "VDD_T9") (pintype "power_in"))
      (node (ref "U15") (pin "A1") (pinfunction "VDDQ_A1") (pintype "power_in"))
      (node (ref "U15") (pin "A9") (pinfunction "VDDQ_A9") (pintype "power_in"))
      (node (ref "U15") (pin "B3") (pinfunction "VDD_B3") (pintype "power_in"))
      (node (ref "U15") (pin "B9") (pinfunction "VDD_B9") (pintype "power_in"))
      (node (ref "U15") (pin "C1") (pinfunction "VDDQ_C1") (pintype "power_in"))
      (node (ref "U15") (pin "D1") (pinfunction "VDD_D1") (pintype "power_in"))
      (node (ref "U15") (pin "D9") (pinfunction "VDDQ_D9") (pintype "power_in"))
      (node (ref "U15") (pin "F2") (pinfunction "VDDQ_F2") (pintype "power_in"))
      (node (ref "U15") (pin "F8") (pinfunction "VDDQ_F8") (pintype "power_in"))
      (node (ref "U15") (pin "G1") (pinfunction "VDDQ_G1") (pintype "power_in"))
      (node (ref "U15") (pin "G7") (pinfunction "VDD_G7") (pintype "power_in"))
      (node (ref "U15") (pin "G9") (pinfunction "VDDQ_G9") (pintype "power_in"))
      (node (ref "U15") (pin "J1") (pinfunction "VDD_J1") (pintype "power_in"))
      (node (ref "U15") (pin "J2") (pinfunction "VDDQ_J2") (pintype "power_in"))
      (node (ref "U15") (pin "J8") (pinfunction "VDDQ_J8") (pintype "power_in"))
      (node (ref "U15") (pin "J9") (pinfunction "VDD_J9") (pintype "power_in"))
      (node (ref "U15") (pin "L1") (pinfunction "VDD_L1") (pintype "power_in"))
      (node (ref "U15") (pin "L9") (pinfunction "VDD_L9") (pintype "power_in"))
      (node (ref "U15") (pin "R1") (pinfunction "VDD_R1") (pintype "power_in"))
      (node (ref "U15") (pin "T9") (pinfunction "VDD_T9") (pintype "power_in"))
    )
    (net (code "92") (name "unconnected-(U14A-NC-PadT7)") (class "Default")
      (node (ref "U14") (pin "T7") (pinfunction "NC_T7") (pintype "passive"))
    )
    (net (code "93") (name "unconnected-(U15A-NC-PadT7)") (class "Default")
      (node (ref "U15") (pin "T7") (pinfunction "NC_T7") (pintype "passive"))
    )
  )
)
